# M1553io.net
KiCad netlist of a schematic drawn in EAGLE
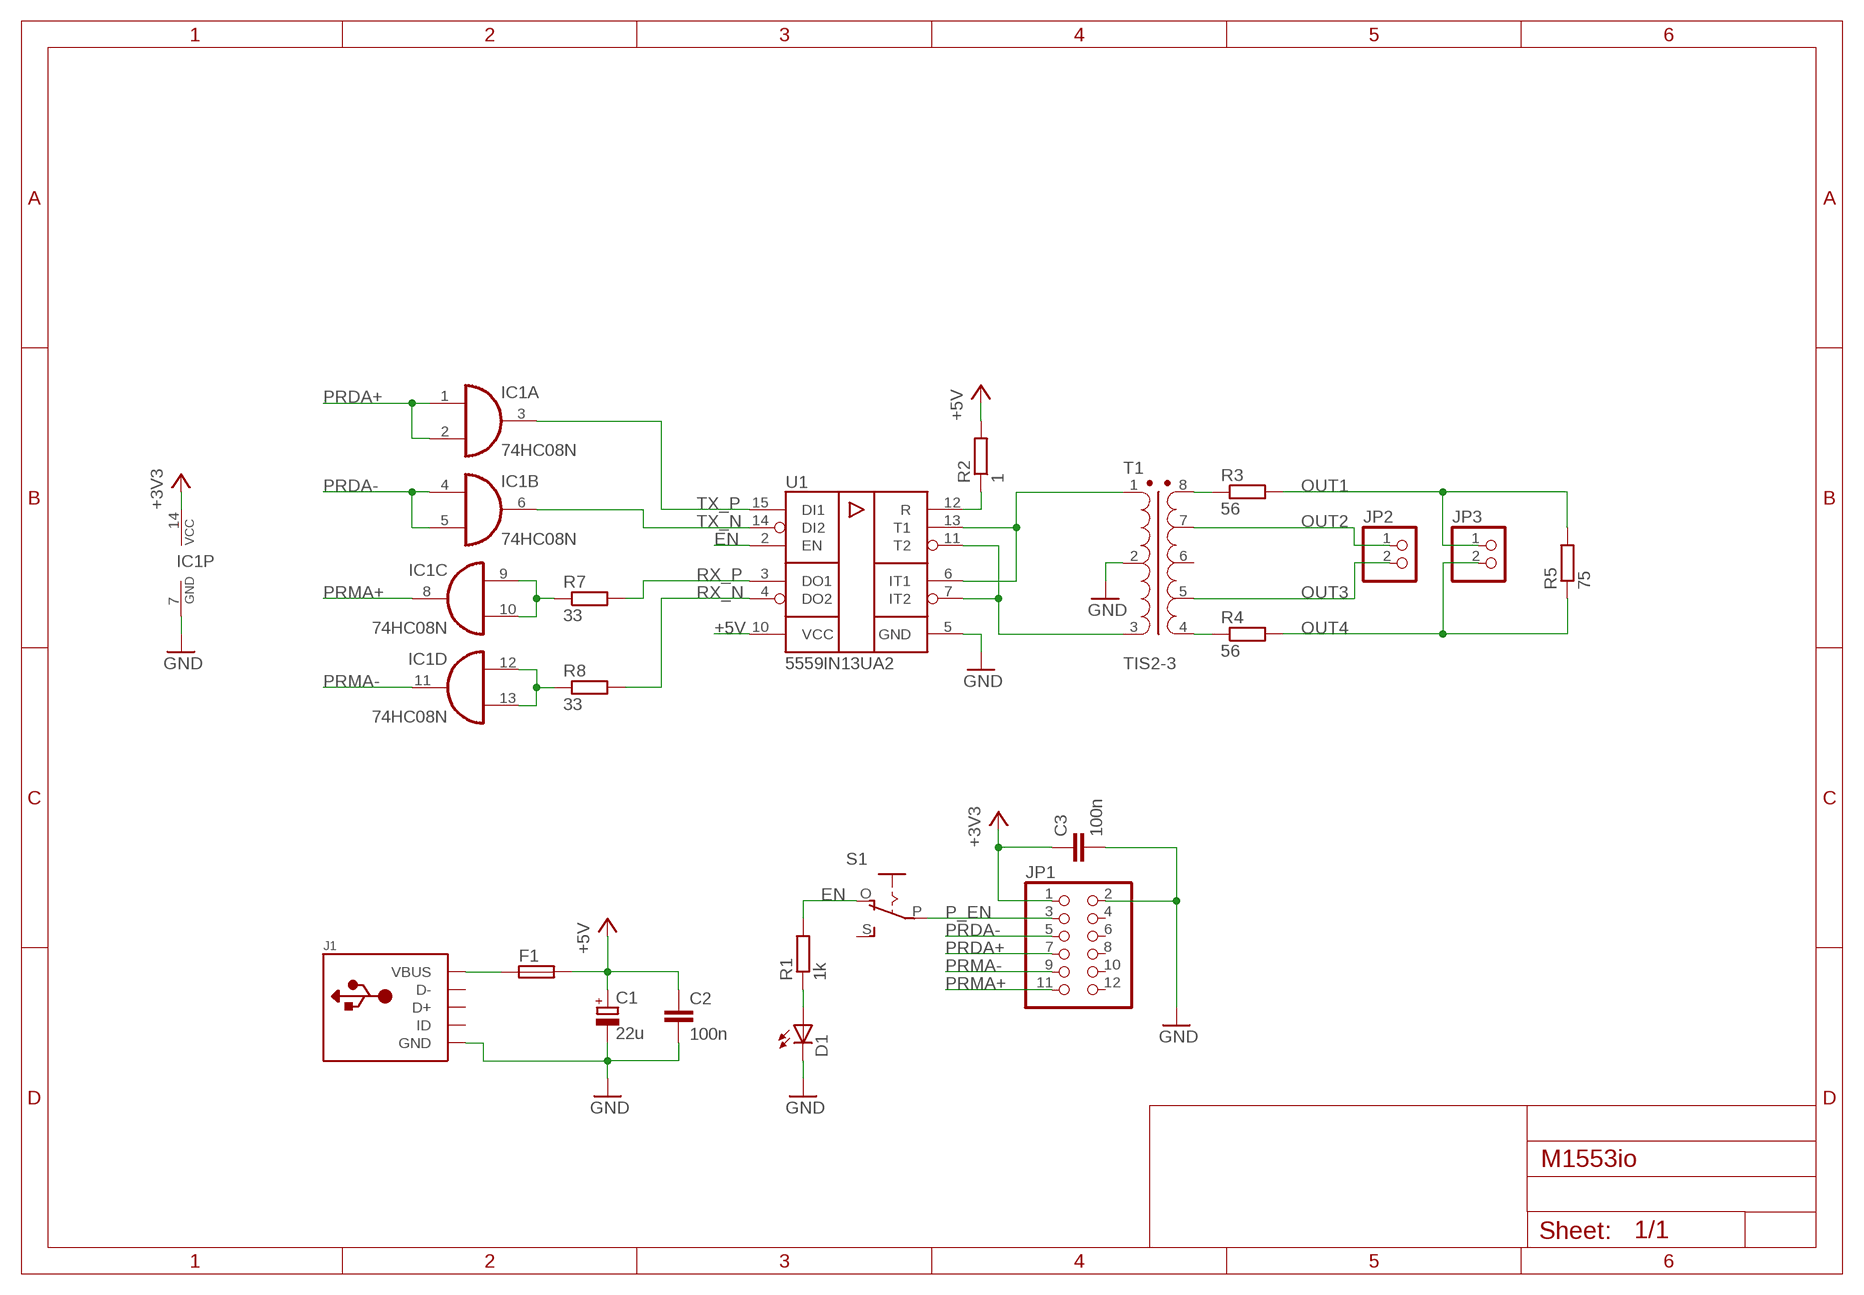
[diagram p0: schematic, sheet 1]

(export (version "E")
  (design (tool "Eeschema 10.0.6"))
  (components
    (comp (ref "C1")
      (value "22u")
      (footprint "eagle-import:RCL-1206F-POL")
      (libsource (lib "eagle-import") (part "CPOL-EU"))
    )
    (comp (ref "C2")
      (value "100n")
      (footprint "eagle-import:RCL-1206F")
      (libsource (lib "eagle-import") (part "C-EU1206"))
    )
    (comp (ref "C3")
      (value "100n")
      (footprint "eagle-import:RCL-1206F")
      (libsource (lib "eagle-import") (part "C-EU1206"))
    )
    (comp (ref "D1")
      (value "LED1206")
      (footprint "eagle-import:LED-1206F")
      (libsource (lib "eagle-import") (part "LED1206"))
    )
    (comp (ref "F1")
      (value "FUSE-NSMF")
      (footprint "eagle-import:RCL-1206F")
      (libsource (lib "eagle-import") (part "FUSE-NSMF"))
    )
    (comp (ref "IC1")
      (value "74HC08N")
      (footprint "eagle-import:DIL14")
      (libsource (lib "eagle-import") (part "7408NHC"))
    )
    (comp (ref "J1")
      (value "USB-MINI")
      (footprint "eagle-import:USB-MINIB")
      (libsource (lib "eagle-import") (part "USB-MINI"))
    )
    (comp (ref "JP1")
      (value "PINHD-2X6")
      (footprint "eagle-import:2X06")
      (libsource (lib "eagle-import") (part "PINHD-2X6"))
    )
    (comp (ref "JP2")
      (value "PINHD-1X2")
      (footprint "eagle-import:1X02")
      (libsource (lib "eagle-import") (part "PINHD-1X2"))
    )
    (comp (ref "JP3")
      (value "PINHD-1X2")
      (footprint "eagle-import:1X02")
      (libsource (lib "eagle-import") (part "PINHD-1X2"))
    )
    (comp (ref "R1")
      (value "1k")
      (footprint "eagle-import:RCL-0805F")
      (libsource (lib "eagle-import") (part "R-EU0805"))
    )
    (comp (ref "R2")
      (value "1")
      (footprint "eagle-import:RCL-0805F")
      (libsource (lib "eagle-import") (part "R-EU0805"))
    )
    (comp (ref "R3")
      (value "56")
      (footprint "eagle-import:RCL-0805F")
      (libsource (lib "eagle-import") (part "R-EU0805"))
    )
    (comp (ref "R4")
      (value "56")
      (footprint "eagle-import:RCL-0805F")
      (libsource (lib "eagle-import") (part "R-EU0805"))
    )
    (comp (ref "R5")
      (value "75")
      (footprint "eagle-import:RCL-0805F")
      (libsource (lib "eagle-import") (part "R-EU0805"))
    )
    (comp (ref "R7")
      (value "33")
      (footprint "eagle-import:RCL-0805F")
      (libsource (lib "eagle-import") (part "R-EU0805"))
    )
    (comp (ref "R8")
      (value "33")
      (footprint "eagle-import:RCL-0805F")
      (libsource (lib "eagle-import") (part "R-EU0805"))
    )
    (comp (ref "S1")
      (value "EG1218S")
      (footprint "eagle-import:EG1218")
      (libsource (lib "eagle-import") (part "EG1218S"))
    )
    (comp (ref "T1")
      (value "TIS2-3")
      (footprint "eagle-import:TIS2-3")
      (libsource (lib "eagle-import") (part "TIS2-3"))
    )
    (comp (ref "U1")
      (value "5559IN13UA2")
      (footprint "eagle-import:5119.16-A")
      (libsource (lib "eagle-import") (part "5559IN13UA2"))
    )
  )
  (nets
    (net (code "1") (name "+3V3") (class "Default")
      (node (ref "C3") (pin "1") (pinfunction "1_1") (pintype "passive"))
      (node (ref "IC1") (pin "14") (pinfunction "VCC_14") (pintype "power_in"))
      (node (ref "JP1") (pin "1") (pinfunction "1_1") (pintype "passive"))
    )
    (net (code "2") (name "+5V") (class "Default")
      (node (ref "C1") (pin "+") (pinfunction "+_+") (pintype "passive"))
      (node (ref "C2") (pin "1") (pinfunction "1_1") (pintype "passive"))
      (node (ref "F1") (pin "2") (pinfunction "2_2") (pintype "passive"))
      (node (ref "R2") (pin "2") (pinfunction "2_2") (pintype "passive"))
      (node (ref "U1") (pin "10") (pinfunction "VCC_10") (pintype "bidirectional"))
    )
    (net (code "3") (name "/EN") (class "Default")
      (node (ref "R1") (pin "2") (pinfunction "2_2") (pintype "passive"))
      (node (ref "S1") (pin "O") (pinfunction "O_O") (pintype "passive"))
      (node (ref "U1") (pin "2") (pinfunction "EN_2") (pintype "bidirectional"))
    )
    (net (code "4") (name "/OUT1") (class "Default")
      (node (ref "JP3") (pin "1") (pinfunction "1_1") (pintype "passive"))
      (node (ref "R3") (pin "2") (pinfunction "2_2") (pintype "passive"))
      (node (ref "R5") (pin "2") (pinfunction "2_2") (pintype "passive"))
    )
    (net (code "5") (name "/OUT2") (class "Default")
      (node (ref "JP2") (pin "1") (pinfunction "1_1") (pintype "passive"))
      (node (ref "T1") (pin "7") (pinfunction "7_7") (pintype "passive"))
    )
    (net (code "6") (name "/OUT3") (class "Default")
      (node (ref "JP2") (pin "2") (pinfunction "2_2") (pintype "passive"))
      (node (ref "T1") (pin "5") (pinfunction "5_5") (pintype "passive"))
    )
    (net (code "7") (name "/OUT4") (class "Default")
      (node (ref "JP3") (pin "2") (pinfunction "2_2") (pintype "passive"))
      (node (ref "R4") (pin "2") (pinfunction "2_2") (pintype "passive"))
      (node (ref "R5") (pin "1") (pinfunction "1_1") (pintype "passive"))
    )
    (net (code "8") (name "/PRDA+") (class "Default")
      (node (ref "IC1") (pin "1") (pinfunction "I0_1") (pintype "input"))
      (node (ref "IC1") (pin "2") (pinfunction "I1_2") (pintype "input"))
      (node (ref "JP1") (pin "7") (pinfunction "7_7") (pintype "passive"))
    )
    (net (code "9") (name "/PRDA-") (class "Default")
      (node (ref "IC1") (pin "4") (pinfunction "I0_4") (pintype "input"))
      (node (ref "IC1") (pin "5") (pinfunction "I1_5") (pintype "input"))
      (node (ref "JP1") (pin "5") (pinfunction "5_5") (pintype "passive"))
    )
    (net (code "10") (name "/PRMA+") (class "Default")
      (node (ref "IC1") (pin "8") (pinfunction "O_8") (pintype "output"))
      (node (ref "JP1") (pin "11") (pinfunction "11_11") (pintype "passive"))
    )
    (net (code "11") (name "/PRMA-") (class "Default")
      (node (ref "IC1") (pin "11") (pinfunction "O_11") (pintype "output"))
      (node (ref "JP1") (pin "9") (pinfunction "9_9") (pintype "passive"))
    )
    (net (code "12") (name "/P_EN") (class "Default")
      (node (ref "JP1") (pin "3") (pinfunction "3_3") (pintype "passive"))
      (node (ref "S1") (pin "P") (pinfunction "P_P") (pintype "passive"))
    )
    (net (code "13") (name "/RX_N") (class "Default")
      (node (ref "R8") (pin "2") (pinfunction "2_2") (pintype "passive"))
      (node (ref "U1") (pin "4") (pinfunction "DO2_4") (pintype "bidirectional"))
    )
    (net (code "14") (name "/RX_P") (class "Default")
      (node (ref "R7") (pin "2") (pinfunction "2_2") (pintype "passive"))
      (node (ref "U1") (pin "3") (pinfunction "DO1_3") (pintype "bidirectional"))
    )
    (net (code "15") (name "/TX_N") (class "Default")
      (node (ref "IC1") (pin "6") (pinfunction "O_6") (pintype "output"))
      (node (ref "U1") (pin "14") (pinfunction "DI2_14") (pintype "bidirectional"))
    )
    (net (code "16") (name "/TX_P") (class "Default")
      (node (ref "IC1") (pin "3") (pinfunction "O_3") (pintype "output"))
      (node (ref "U1") (pin "15") (pinfunction "DI1_15") (pintype "bidirectional"))
    )
    (net (code "17") (name "GND") (class "Default")
      (node (ref "C1") (pin "-") (pinfunction "-_-") (pintype "passive"))
      (node (ref "C2") (pin "2") (pinfunction "2_2") (pintype "passive"))
      (node (ref "C3") (pin "2") (pinfunction "2_2") (pintype "passive"))
      (node (ref "D1") (pin "C") (pinfunction "C_C") (pintype "passive"))
      (node (ref "IC1") (pin "7") (pinfunction "GND_7") (pintype "power_in"))
      (node (ref "J1") (pin "GND") (pinfunction "GND_GND") (pintype "power_in"))
      (node (ref "JP1") (pin "2") (pinfunction "2_2") (pintype "passive"))
      (node (ref "T1") (pin "2") (pinfunction "2_2") (pintype "passive"))
      (node (ref "U1") (pin "5") (pinfunction "GND_5") (pintype "bidirectional"))
    )
    (net (code "18") (name "Net-(D1-PadA)") (class "Default")
      (node (ref "D1") (pin "A") (pinfunction "A_A") (pintype "passive"))
      (node (ref "R1") (pin "1") (pinfunction "1_1") (pintype "passive"))
    )
    (net (code "19") (name "Net-(F1-Pad1)") (class "Default")
      (node (ref "F1") (pin "1") (pinfunction "1_1") (pintype "passive"))
      (node (ref "J1") (pin "VBUS") (pinfunction "VBUS_VBUS") (pintype "power_in"))
    )
    (net (code "20") (name "Net-(IC1C-I0)") (class "Default")
      (node (ref "IC1") (pin "10") (pinfunction "I1_10") (pintype "input"))
      (node (ref "IC1") (pin "9") (pinfunction "I0_9") (pintype "input"))
      (node (ref "R7") (pin "1") (pinfunction "1_1") (pintype "passive"))
    )
    (net (code "21") (name "Net-(IC1D-I0)") (class "Default")
      (node (ref "IC1") (pin "12") (pinfunction "I0_12") (pintype "input"))
      (node (ref "IC1") (pin "13") (pinfunction "I1_13") (pintype "input"))
      (node (ref "R8") (pin "1") (pinfunction "1_1") (pintype "passive"))
    )
    (net (code "22") (name "Net-(R3-Pad1)") (class "Default")
      (node (ref "R3") (pin "1") (pinfunction "1_1") (pintype "passive"))
      (node (ref "T1") (pin "8") (pinfunction "8_8") (pintype "passive"))
    )
    (net (code "23") (name "Net-(R4-Pad1)") (class "Default")
      (node (ref "R4") (pin "1") (pinfunction "1_1") (pintype "passive"))
      (node (ref "T1") (pin "4") (pinfunction "4_4") (pintype "passive"))
    )
    (net (code "24") (name "Net-(U1-IT1)") (class "Default")
      (node (ref "T1") (pin "1") (pinfunction "1_1") (pintype "passive"))
      (node (ref "U1") (pin "13") (pinfunction "T1_13") (pintype "bidirectional"))
      (node (ref "U1") (pin "6") (pinfunction "IT1_6") (pintype "bidirectional"))
    )
    (net (code "25") (name "Net-(U1-IT2)") (class "Default")
      (node (ref "T1") (pin "3") (pinfunction "3_3") (pintype "passive"))
      (node (ref "U1") (pin "11") (pinfunction "T2_11") (pintype "bidirectional"))
      (node (ref "U1") (pin "7") (pinfunction "IT2_7") (pintype "bidirectional"))
    )
    (net (code "26") (name "Net-(U1-R)") (class "Default")
      (node (ref "R2") (pin "1") (pinfunction "1_1") (pintype "passive"))
      (node (ref "U1") (pin "12") (pinfunction "R_12") (pintype "bidirectional"))
    )
    (net (code "27") (name "unconnected-(J1-PadD+)") (class "Default")
      (node (ref "J1") (pin "D+") (pinfunction "D+_D+") (pintype "bidirectional"))
    )
    (net (code "28") (name "unconnected-(J1-PadD-)") (class "Default")
      (node (ref "J1") (pin "D-") (pinfunction "D-_D-") (pintype "bidirectional"))
    )
    (net (code "29") (name "unconnected-(J1-PadID)") (class "Default")
      (node (ref "J1") (pin "ID") (pinfunction "ID_ID") (pintype "bidirectional"))
    )
    (net (code "30") (name "unconnected-(JP1-Pad4)") (class "Default")
      (node (ref "JP1") (pin "4") (pinfunction "4_4") (pintype "passive"))
    )
    (net (code "31") (name "unconnected-(JP1-Pad6)") (class "Default")
      (node (ref "JP1") (pin "6") (pinfunction "6_6") (pintype "passive"))
    )
    (net (code "32") (name "unconnected-(JP1-Pad8)") (class "Default")
      (node (ref "JP1") (pin "8") (pinfunction "8_8") (pintype "passive"))
    )
    (net (code "33") (name "unconnected-(JP1-Pad10)") (class "Default")
      (node (ref "JP1") (pin "10") (pinfunction "10_10") (pintype "passive"))
    )
    (net (code "34") (name "unconnected-(JP1-Pad12)") (class "Default")
      (node (ref "JP1") (pin "12") (pinfunction "12_12") (pintype "passive"))
    )
    (net (code "35") (name "unconnected-(S1-PadS)") (class "Default")
      (node (ref "S1") (pin "S") (pinfunction "S_S") (pintype "passive"))
    )
    (net (code "36") (name "unconnected-(T1-Pad6)") (class "Default")
      (node (ref "T1") (pin "6") (pinfunction "6_6") (pintype "passive"))
    )
  )
)
